# Alimentacion.net
KiCad netlist of a schematic drawn in Altium Designer
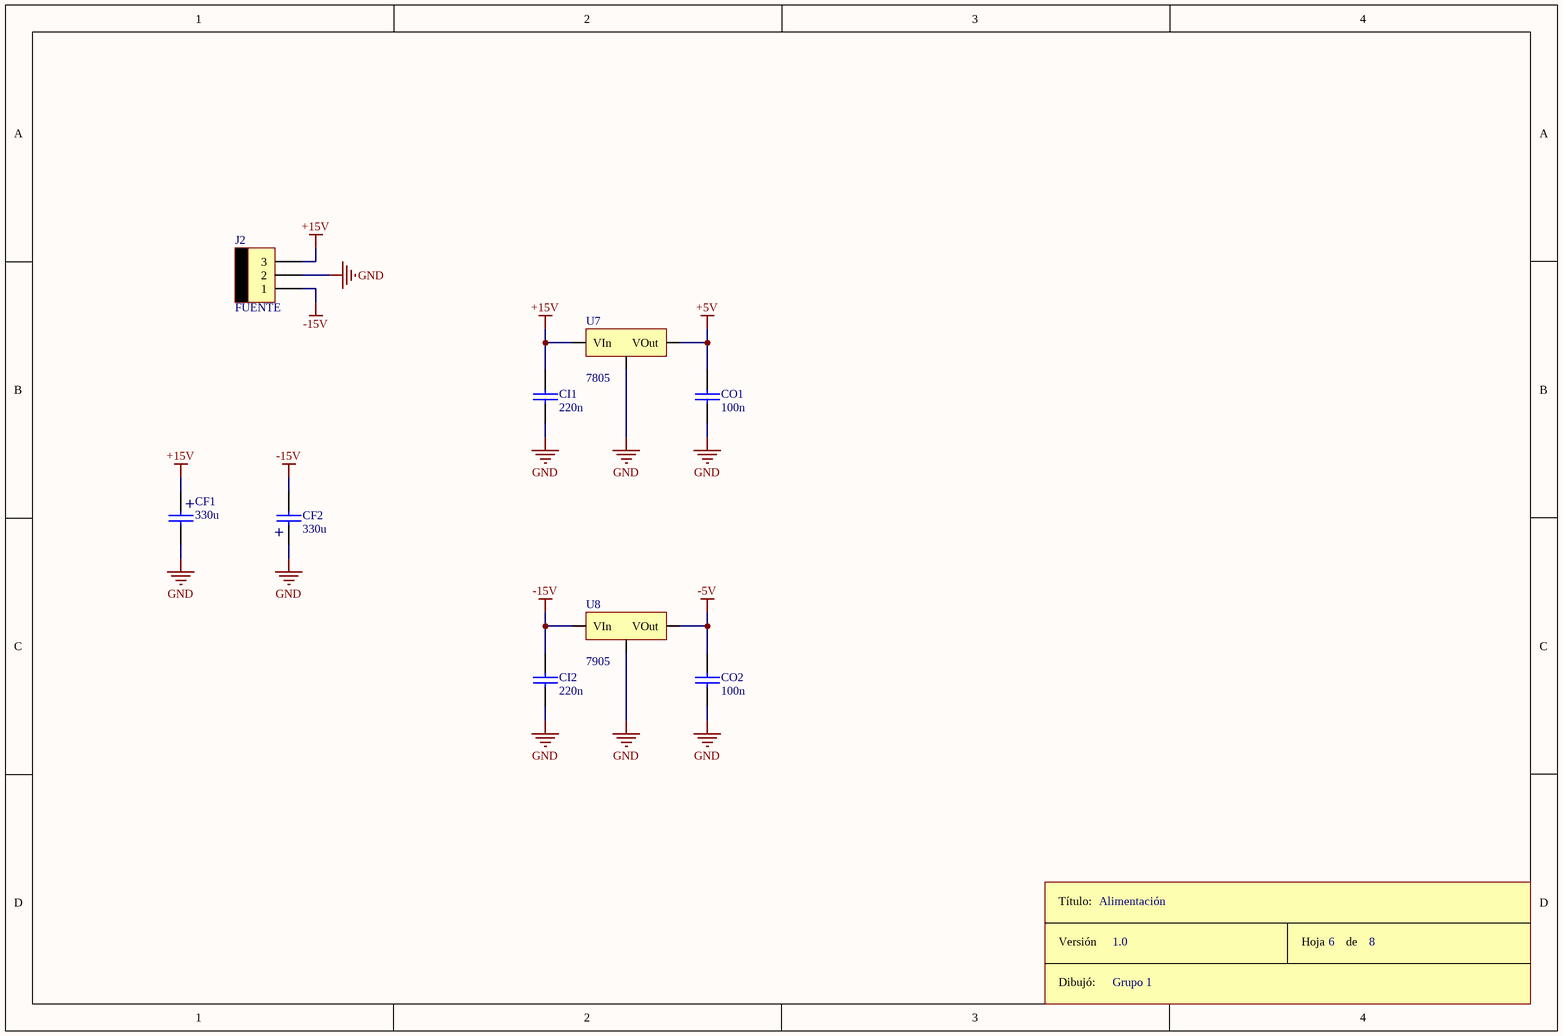
[diagram p0: Alimentacion.SchDoc]

(export (version "E")
  (design (tool "Eeschema 10.0.6"))
  (components
    (comp (ref "CF1") (value "330u") (footprint "CAP200RP") (libsource (lib "LIBEBAL") (part "CAPPOL")))
    (comp (ref "CF2") (value "330u") (footprint "CAP200RP") (libsource (lib "LIBEBAL") (part "CAPPOL")))
    (comp (ref "CI1") (value "220n") (footprint "CAP100") (libsource (lib "LIBEBAL") (part "CAP")))
    (comp (ref "CI2") (value "220n") (footprint "CAP100") (libsource (lib "LIBEBAL") (part "CAP")))
    (comp (ref "CO1") (value "100n") (footprint "CAP100") (libsource (lib "LIBEBAL") (part "CAP")))
    (comp (ref "CO2") (value "100n") (footprint "CAP100") (libsource (lib "LIBEBAL") (part "CAP")))
    (comp (ref "J2") (value "FUENTE") (footprint "MOLEX3") (libsource (lib "LIBEBAL") (part "MOLEX3")))
    (comp (ref "ROT5") (value "Rótulo") (libsource (lib "LIB PIO IX") (part "Rótulo")))
    (comp (ref "U7")
      (value "7805")
      (footprint "TO-220 V")
      (description "REGULDOR POSITIVO")
      (libsource (lib "LIBEBAL") (part "78XX"))
    )
    (comp (ref "U8")
      (value "7905")
      (footprint "TO-220 V")
      (description "REGULADOR NEGATIVO")
      (libsource (lib "LIBEBAL") (part "79XX"))
    )
  )
  (nets
    (net (code "1") (name "+5V") (class "Default")
      (node (ref "CO1") (pin "1") (pinfunction "1_1") (pintype "passive"))
      (node (ref "U7") (pin "3") (pinfunction "VOut_3") (pintype "passive"))
    )
    (net (code "2") (name "+15V") (class "Default")
      (node (ref "CF1") (pin "1") (pinfunction "1_1") (pintype "passive"))
      (node (ref "CI1") (pin "1") (pinfunction "1_1") (pintype "passive"))
      (node (ref "J2") (pin "3") (pinfunction "3_3") (pintype "passive"))
      (node (ref "U7") (pin "1") (pinfunction "VIn_1") (pintype "passive"))
    )
    (net (code "3") (name "-5V") (class "Default")
      (node (ref "CO2") (pin "1") (pinfunction "1_1") (pintype "passive"))
      (node (ref "U8") (pin "3") (pinfunction "VOut_3") (pintype "passive"))
    )
    (net (code "4") (name "-15V") (class "Default")
      (node (ref "CF2") (pin "2") (pinfunction "2_2") (pintype "passive"))
      (node (ref "CI2") (pin "1") (pinfunction "1_1") (pintype "passive"))
      (node (ref "J2") (pin "1") (pinfunction "1_1") (pintype "passive"))
      (node (ref "U8") (pin "2") (pinfunction "VIn_2") (pintype "passive"))
    )
    (net (code "5") (name "GND") (class "Default")
      (node (ref "CF1") (pin "2") (pinfunction "2_2") (pintype "passive"))
      (node (ref "CF2") (pin "1") (pinfunction "1_1") (pintype "passive"))
      (node (ref "CI1") (pin "2") (pinfunction "2_2") (pintype "passive"))
      (node (ref "CI2") (pin "2") (pinfunction "2_2") (pintype "passive"))
      (node (ref "CO1") (pin "2") (pinfunction "2_2") (pintype "passive"))
      (node (ref "CO2") (pin "2") (pinfunction "2_2") (pintype "passive"))
      (node (ref "J2") (pin "2") (pinfunction "2_2") (pintype "passive"))
      (node (ref "U7") (pin "2") (pinfunction "GND_2") (pintype "passive"))
      (node (ref "U8") (pin "1") (pinfunction "GND_1") (pintype "passive"))
    )
  )
)
